# Power_Management.net
KiCad netlist of a schematic drawn in Altium Designer
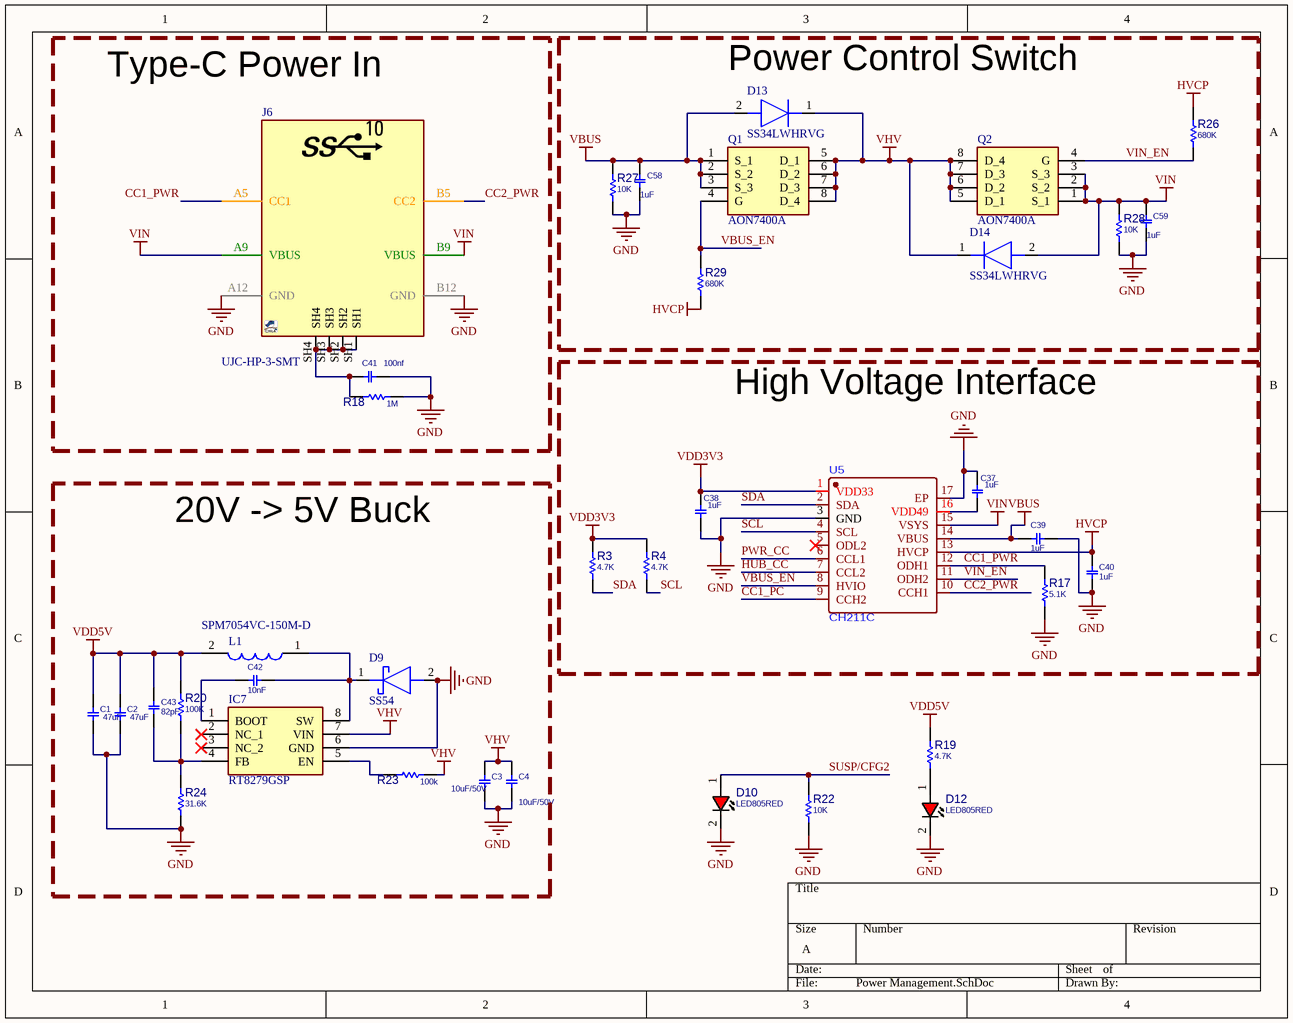
[diagram p0: Power Management.SchDoc]

(export (version "E")
  (design (tool "Eeschema 10.0.6"))
  (components
    (comp (ref "C1")
      (value "47uF")
      (footprint "C0805")
      (libsource (lib "passive_smd") (part "CAP_SMD_MLCC_0805"))
    )
    (comp (ref "C2")
      (value "47uF")
      (footprint "C0805")
      (libsource (lib "passive_smd") (part "CAP_SMD_MLCC_0805"))
    )
    (comp (ref "C3")
      (value "10uF/50V")
      (footprint "C0805")
      (libsource (lib "passive_smd") (part "CAP_SMD_MLCC_0805"))
    )
    (comp (ref "C4")
      (value "10uF/50V")
      (footprint "C0805")
      (description "50V")
      (libsource (lib "passive_smd") (part "CAP_SMD_MLCC_0402"))
    )
    (comp (ref "C37")
      (value "1uF")
      (footprint "C0805")
      (libsource (lib "passive_smd") (part "CAP_SMD_MLCC_0805"))
    )
    (comp (ref "C38")
      (value "1uF")
      (footprint "C0805")
      (libsource (lib "passive_smd") (part "CAP_SMD_MLCC_0805"))
    )
    (comp (ref "C39")
      (value "1uF")
      (footprint "C0805")
      (libsource (lib "passive_smd") (part "CAP_SMD_MLCC_0805"))
    )
    (comp (ref "C40")
      (value "1uF")
      (footprint "C0805")
      (libsource (lib "passive_smd") (part "CAP_SMD_MLCC_0805"))
    )
    (comp (ref "C41")
      (value "100nf")
      (footprint "C1812")
      (description "+1kv 100nf")
      (libsource (lib "passive_smd") (part "CAP_SMD_MLCC_1812"))
    )
    (comp (ref "C42")
      (value "10nF")
      (footprint "C0402")
      (libsource (lib "passive_smd") (part "CAP_SMD_MLCC_0402"))
    )
    (comp (ref "C43")
      (value "82pF")
      (footprint "C0402")
      (libsource (lib "passive_smd") (part "CAP_SMD_MLCC_0402"))
    )
    (comp (ref "C58")
      (value "1uF")
      (footprint "C0402")
      (libsource (lib "passive_smd") (part "CAP_SMD_MLCC_0402"))
    )
    (comp (ref "C59")
      (value "1uF")
      (footprint "C0402")
      (libsource (lib "passive_smd") (part "CAP_SMD_MLCC_0402"))
    )
    (comp (ref "D9")
      (value "SS54")
      (footprint "SamacSys:DIOM5026X262N")
      (description "Schottky Diode")
      (libsource (lib "*") (part "SS54"))
    )
    (comp (ref "D10")
      (value "LED805RED")
      (footprint "LED0805RED")
      (description "LED, SMD, 0805, RED")
      (fields (field (name "MANF") "MANF") (field (name "MANF_P#") "MANF_PART#"))
      (libsource (lib "led(diode)") (part "LED_SMD_0805_RED"))
    )
    (comp (ref "D12")
      (value "LED805RED")
      (footprint "LED0805RED")
      (description "LED, SMD, 0805, RED")
      (fields (field (name "MANF") "MANF") (field (name "MANF_P#") "MANF_PART#"))
      (libsource (lib "led(diode)") (part "LED_SMD_0805_RED"))
    )
    (comp (ref "D13")
      (value "SS34LWHRVG")
      (footprint "SamacSys:SODFL3718X102N")
      (description "Diode")
      (fields (field (name "MOUSER PART NUMBER") "821-SS34LWHRVG"))
      (libsource (lib "*") (part "SS34LWHRVG"))
    )
    (comp (ref "D14")
      (value "SS34LWHRVG")
      (footprint "SamacSys:SODFL3718X102N")
      (description "Diode")
      (fields (field (name "MOUSER PART NUMBER") "821-SS34LWHRVG"))
      (libsource (lib "*") (part "SS34LWHRVG"))
    )
    (comp (ref "IC7")
      (value "RT8279GSP")
      (footprint "SamacSys:SOIC127P600X175-8N")
      (description "Integrated Circuit")
      (libsource (lib "*") (part "RT8279GSP"))
    )
    (comp (ref "J6")
      (value "UJC-HP-3-SMT")
      (footprint "USBC_SMD_6_UJCHP3SMT")
      (description "CONN, USB, Type C (USB 3.1), Right-Angle, SMD")
      (fields (field (name "MANF") "CUI Devices"))
      (libsource (lib "conn_usbc") (part "CONN_USBC_SMD_6_UJC-HP-3-SMT"))
    )
    (comp (ref "L1")
      (value "SPM7054VC-150M-D")
      (footprint "SamacSys:SPM7054VC150MD")
      (description "Inductor")
      (fields (field (name "MOUSER PART NUMBER") "810-SPM7054VC-150M-D"))
      (libsource (lib "*") (part "SPM7054VC-150M-D"))
    )
    (comp (ref "Q1")
      (value "AON7400A")
      (footprint "SamacSys:DFN_3X3_EP")
      (description "MOSFET (N-Channel)")
      (libsource (lib "*") (part "AON7400A"))
    )
    (comp (ref "Q2")
      (value "AON7400A")
      (footprint "SamacSys:DFN_3X3_EP")
      (description "MOSFET (N-Channel)")
      (libsource (lib "") (part "AON7400A_1"))
    )
    (comp (ref "R3")
      (value "4.7K")
      (footprint "R0402")
      (description "RESISTOR, SMD")
      (libsource (lib "passive_smd") (part "RES_SMD_0402"))
    )
    (comp (ref "R4")
      (value "4.7K")
      (footprint "R0402")
      (description "RESISTOR, SMD")
      (libsource (lib "passive_smd") (part "RES_SMD_0402"))
    )
    (comp (ref "R17")
      (value "5.1K")
      (footprint "R0402")
      (description "RESISTOR, SMD")
      (libsource (lib "passive_smd") (part "RES_SMD_0402"))
    )
    (comp (ref "R18")
      (value "1M")
      (footprint "R0805")
      (description "RESISTOR, SMD\r\n0805")
      (libsource (lib "passive_smd") (part "RES_SMD_0402"))
    )
    (comp (ref "R19")
      (value "4.7K")
      (footprint "R0402")
      (description "RESISTOR, SMD")
      (libsource (lib "passive_smd") (part "RES_SMD_0402"))
    )
    (comp (ref "R20")
      (value "100K")
      (footprint "R0402")
      (description "RESISTOR, SMD")
      (libsource (lib "passive_smd") (part "RES_SMD_0402"))
    )
    (comp (ref "R22")
      (value "10K")
      (footprint "R0402")
      (description "RESISTOR, SMD")
      (libsource (lib "passive_smd") (part "RES_SMD_0402"))
    )
    (comp (ref "R23")
      (value "100k")
      (footprint "R0402")
      (description "RESISTOR, SMD")
      (libsource (lib "passive_smd") (part "RES_SMD_0402"))
    )
    (comp (ref "R24")
      (value "31.6K")
      (footprint "R0402")
      (description "RESISTOR, SMD")
      (libsource (lib "passive_smd") (part "RES_SMD_0402"))
    )
    (comp (ref "R26")
      (value "680K")
      (footprint "R0402")
      (description "RESISTOR, SMD")
      (libsource (lib "passive_smd") (part "RES_SMD_0402"))
    )
    (comp (ref "R27")
      (value "10K")
      (footprint "R0402")
      (description "RESISTOR, SMD")
      (libsource (lib "passive_smd") (part "RES_SMD_0402"))
    )
    (comp (ref "R28")
      (value "10K")
      (footprint "R0402")
      (description "RESISTOR, SMD")
      (libsource (lib "passive_smd") (part "RES_SMD_0402"))
    )
    (comp (ref "R29")
      (value "680K")
      (footprint "R0402")
      (description "RESISTOR, SMD")
      (libsource (lib "passive_smd") (part "RES_SMD_0402"))
    )
    (comp (ref "U5")
      (value "CH211C")
      (footprint "QFN-16C_L2.0-W2.0-P0.40-BL-EP1.2")
      (libsource (lib "Schlib1") (part "CH211C"))
    )
  )
  (nets
    (net (code "1") (name "/CC1_PC") (class "Default")
      (node (ref "U5") (pin "9") (pinfunction "CCH2_9") (pintype "passive"))
    )
    (net (code "2") (name "/CC1_PWR") (class "Default")
      (node (ref "J6") (pin "A5") (pinfunction "CC1_A5") (pintype "passive"))
      (node (ref "R17") (pin "1") (pinfunction "1_1") (pintype "passive"))
      (node (ref "U5") (pin "12") (pinfunction "ODH1_12") (pintype "passive"))
    )
    (net (code "3") (name "/CC2_PWR") (class "Default")
      (node (ref "J6") (pin "B5") (pinfunction "CC2_B5") (pintype "passive"))
      (node (ref "U5") (pin "10") (pinfunction "CCH1_10") (pintype "passive"))
    )
    (net (code "4") (name "/HUB_CC") (class "Default")
      (node (ref "U5") (pin "7") (pinfunction "CCL2_7") (pintype "passive"))
    )
    (net (code "5") (name "/PWR_CC") (class "Default")
      (node (ref "U5") (pin "6") (pinfunction "CCL1_6") (pintype "passive"))
    )
    (net (code "6") (name "/SCL") (class "Default")
      (node (ref "R4") (pin "2") (pinfunction "2_2") (pintype "passive"))
      (node (ref "U5") (pin "4") (pinfunction "SCL_4") (pintype "passive"))
    )
    (net (code "7") (name "/SDA") (class "Default")
      (node (ref "R3") (pin "2") (pinfunction "2_2") (pintype "passive"))
      (node (ref "U5") (pin "2") (pinfunction "SDA_2") (pintype "passive"))
    )
    (net (code "8") (name "/SUSP{slash}CFG2") (class "Default")
      (node (ref "D10") (pin "1") (pinfunction "ANODE_1") (pintype "passive"))
      (node (ref "R22") (pin "1") (pinfunction "1_1") (pintype "passive"))
    )
    (net (code "9") (name "/VBUS_EN") (class "Default")
      (node (ref "Q1") (pin "4") (pinfunction "G_4") (pintype "passive"))
      (node (ref "R29") (pin "1") (pinfunction "1_1") (pintype "passive"))
      (node (ref "U5") (pin "8") (pinfunction "HVIO_8") (pintype "passive"))
    )
    (net (code "10") (name "/VIN_EN") (class "Default")
      (node (ref "Q2") (pin "4") (pinfunction "G_4") (pintype "passive"))
      (node (ref "R26") (pin "1") (pinfunction "1_1") (pintype "passive"))
      (node (ref "U5") (pin "11") (pinfunction "ODH2_11") (pintype "passive"))
    )
    (net (code "11") (name "GND") (class "Default")
      (node (ref "C1") (pin "1") (pinfunction "1_1") (pintype "passive"))
      (node (ref "C2") (pin "1") (pinfunction "1_1") (pintype "passive"))
      (node (ref "C3") (pin "1") (pinfunction "1_1") (pintype "passive"))
      (node (ref "C37") (pin "2") (pinfunction "2_2") (pintype "passive"))
      (node (ref "C38") (pin "1") (pinfunction "1_1") (pintype "passive"))
      (node (ref "C39") (pin "1") (pinfunction "1_1") (pintype "passive"))
      (node (ref "C4") (pin "1") (pinfunction "1_1") (pintype "passive"))
      (node (ref "C40") (pin "2") (pinfunction "2_2") (pintype "passive"))
      (node (ref "C41") (pin "2") (pinfunction "2_2") (pintype "passive"))
      (node (ref "C58") (pin "1") (pinfunction "1_1") (pintype "passive"))
      (node (ref "C59") (pin "1") (pinfunction "1_1") (pintype "passive"))
      (node (ref "D10") (pin "2") (pinfunction "CATHODE_2") (pintype "passive"))
      (node (ref "D12") (pin "2") (pinfunction "CATHODE_2") (pintype "passive"))
      (node (ref "D9") (pin "2") (pinfunction "A_2") (pintype "passive"))
      (node (ref "IC7") (pin "6") (pinfunction "GND_6") (pintype "passive"))
      (node (ref "J6") (pin "A12") (pinfunction "GND_A12") (pintype "passive"))
      (node (ref "J6") (pin "B12") (pinfunction "GND_B12") (pintype "passive"))
      (node (ref "R17") (pin "2") (pinfunction "2_2") (pintype "passive"))
      (node (ref "R18") (pin "1") (pinfunction "1_1") (pintype "passive"))
      (node (ref "R22") (pin "2") (pinfunction "2_2") (pintype "passive"))
      (node (ref "R24") (pin "2") (pinfunction "2_2") (pintype "passive"))
      (node (ref "R27") (pin "2") (pinfunction "2_2") (pintype "passive"))
      (node (ref "R28") (pin "2") (pinfunction "2_2") (pintype "passive"))
      (node (ref "U5") (pin "17") (pinfunction "EP_17") (pintype "passive"))
      (node (ref "U5") (pin "3") (pinfunction "GND_3") (pintype "passive"))
    )
    (net (code "12") (name "HVCP") (class "Default")
      (node (ref "C40") (pin "1") (pinfunction "1_1") (pintype "passive"))
      (node (ref "R26") (pin "2") (pinfunction "2_2") (pintype "passive"))
      (node (ref "R29") (pin "2") (pinfunction "2_2") (pintype "passive"))
      (node (ref "U5") (pin "13") (pinfunction "HVCP_13") (pintype "passive"))
    )
    (net (code "13") (name "Net-(C41-Pad1)") (class "Default")
      (node (ref "C41") (pin "1") (pinfunction "1_1") (pintype "passive"))
      (node (ref "J6") (pin "SH1") (pinfunction "SH1_SH1") (pintype "passive"))
      (node (ref "J6") (pin "SH2") (pinfunction "SH2_SH2") (pintype "passive"))
      (node (ref "J6") (pin "SH3") (pinfunction "SH3_SH3") (pintype "passive"))
      (node (ref "J6") (pin "SH4") (pinfunction "SH4_SH4") (pintype "passive"))
      (node (ref "R18") (pin "2") (pinfunction "2_2") (pintype "passive"))
    )
    (net (code "14") (name "Net-(D9-K)") (class "Default")
      (node (ref "C42") (pin "1") (pinfunction "1_1") (pintype "passive"))
      (node (ref "D9") (pin "1") (pinfunction "K_1") (pintype "passive"))
      (node (ref "IC7") (pin "8") (pinfunction "SW_8") (pintype "passive"))
      (node (ref "L1") (pin "1") (pinfunction "1_1") (pintype "passive"))
    )
    (net (code "15") (name "Net-(D12-ANODE)") (class "Default")
      (node (ref "D12") (pin "1") (pinfunction "ANODE_1") (pintype "passive"))
      (node (ref "R19") (pin "2") (pinfunction "2_2") (pintype "passive"))
    )
    (net (code "16") (name "Net-(IC7-BOOT)") (class "Default")
      (node (ref "C42") (pin "2") (pinfunction "2_2") (pintype "passive"))
      (node (ref "IC7") (pin "1") (pinfunction "BOOT_1") (pintype "passive"))
    )
    (net (code "17") (name "Net-(IC7-EN)") (class "Default")
      (node (ref "IC7") (pin "5") (pinfunction "EN_5") (pintype "passive"))
      (node (ref "R23") (pin "2") (pinfunction "2_2") (pintype "passive"))
    )
    (net (code "18") (name "Net-(IC7-FB)") (class "Default")
      (node (ref "C43") (pin "2") (pinfunction "2_2") (pintype "passive"))
      (node (ref "IC7") (pin "4") (pinfunction "FB_4") (pintype "passive"))
      (node (ref "R20") (pin "2") (pinfunction "2_2") (pintype "passive"))
      (node (ref "R24") (pin "1") (pinfunction "1_1") (pintype "passive"))
    )
    (net (code "19") (name "Net-(U5-VDD49)") (class "Default")
      (node (ref "C37") (pin "1") (pinfunction "1_1") (pintype "passive"))
      (node (ref "U5") (pin "16") (pinfunction "VDD49_16") (pintype "passive"))
    )
    (net (code "20") (name "VBUS") (class "Default")
      (node (ref "C39") (pin "2") (pinfunction "2_2") (pintype "passive"))
      (node (ref "C58") (pin "2") (pinfunction "2_2") (pintype "passive"))
      (node (ref "D13") (pin "2") (pinfunction "A_2") (pintype "passive"))
      (node (ref "Q1") (pin "1") (pinfunction "S_1_1") (pintype "passive"))
      (node (ref "Q1") (pin "2") (pinfunction "S_2_2") (pintype "passive"))
      (node (ref "Q1") (pin "3") (pinfunction "S_3_3") (pintype "passive"))
      (node (ref "R27") (pin "1") (pinfunction "1_1") (pintype "passive"))
      (node (ref "U5") (pin "14") (pinfunction "VBUS_14") (pintype "passive"))
    )
    (net (code "21") (name "VDD3V3") (class "Default")
      (node (ref "C38") (pin "2") (pinfunction "2_2") (pintype "passive"))
      (node (ref "R3") (pin "1") (pinfunction "1_1") (pintype "passive"))
      (node (ref "R4") (pin "1") (pinfunction "1_1") (pintype "passive"))
      (node (ref "U5") (pin "1") (pinfunction "VDD33_1") (pintype "passive"))
    )
    (net (code "22") (name "VDD5V") (class "Default")
      (node (ref "C1") (pin "2") (pinfunction "2_2") (pintype "passive"))
      (node (ref "C2") (pin "2") (pinfunction "2_2") (pintype "passive"))
      (node (ref "C43") (pin "1") (pinfunction "1_1") (pintype "passive"))
      (node (ref "L1") (pin "2") (pinfunction "2_2") (pintype "passive"))
      (node (ref "R19") (pin "1") (pinfunction "1_1") (pintype "passive"))
      (node (ref "R20") (pin "1") (pinfunction "1_1") (pintype "passive"))
    )
    (net (code "23") (name "VHV") (class "Default")
      (node (ref "C3") (pin "2") (pinfunction "2_2") (pintype "passive"))
      (node (ref "C4") (pin "2") (pinfunction "2_2") (pintype "passive"))
      (node (ref "D13") (pin "1") (pinfunction "K_1") (pintype "passive"))
      (node (ref "D14") (pin "1") (pinfunction "K_1") (pintype "passive"))
      (node (ref "IC7") (pin "7") (pinfunction "VIN_7") (pintype "passive"))
      (node (ref "Q1") (pin "5") (pinfunction "D_1_5") (pintype "passive"))
      (node (ref "Q1") (pin "6") (pinfunction "D_2_6") (pintype "passive"))
      (node (ref "Q1") (pin "7") (pinfunction "D_3_7") (pintype "passive"))
      (node (ref "Q1") (pin "8") (pinfunction "D_4_8") (pintype "passive"))
      (node (ref "Q2") (pin "5") (pinfunction "D_1_5") (pintype "passive"))
      (node (ref "Q2") (pin "6") (pinfunction "D_2_6") (pintype "passive"))
      (node (ref "Q2") (pin "7") (pinfunction "D_3_7") (pintype "passive"))
      (node (ref "Q2") (pin "8") (pinfunction "D_4_8") (pintype "passive"))
      (node (ref "R23") (pin "1") (pinfunction "1_1") (pintype "passive"))
    )
    (net (code "24") (name "VIN") (class "Default")
      (node (ref "C59") (pin "2") (pinfunction "2_2") (pintype "passive"))
      (node (ref "D14") (pin "2") (pinfunction "A_2") (pintype "passive"))
      (node (ref "J6") (pin "A9") (pinfunction "VBUS_A9") (pintype "passive"))
      (node (ref "J6") (pin "B9") (pinfunction "VBUS_B9") (pintype "passive"))
      (node (ref "Q2") (pin "1") (pinfunction "S_1_1") (pintype "passive"))
      (node (ref "Q2") (pin "2") (pinfunction "S_2_2") (pintype "passive"))
      (node (ref "Q2") (pin "3") (pinfunction "S_3_3") (pintype "passive"))
      (node (ref "R28") (pin "1") (pinfunction "1_1") (pintype "passive"))
      (node (ref "U5") (pin "15") (pinfunction "VSYS_15") (pintype "passive"))
    )
    (net (code "25") (name "unconnected-(IC7-NC_1-Pad2)") (class "Default")
      (node (ref "IC7") (pin "2") (pinfunction "NC_1_2") (pintype "passive+no_connect"))
    )
    (net (code "26") (name "unconnected-(IC7-NC_2-Pad3)") (class "Default")
      (node (ref "IC7") (pin "3") (pinfunction "NC_2_3") (pintype "passive+no_connect"))
    )
    (net (code "27") (name "unconnected-(U5-ODL2-Pad5)") (class "Default")
      (node (ref "U5") (pin "5") (pinfunction "ODL2_5") (pintype "passive+no_connect"))
    )
  )
)
